# ads.net
KiCad netlist of a schematic drawn in EAGLE
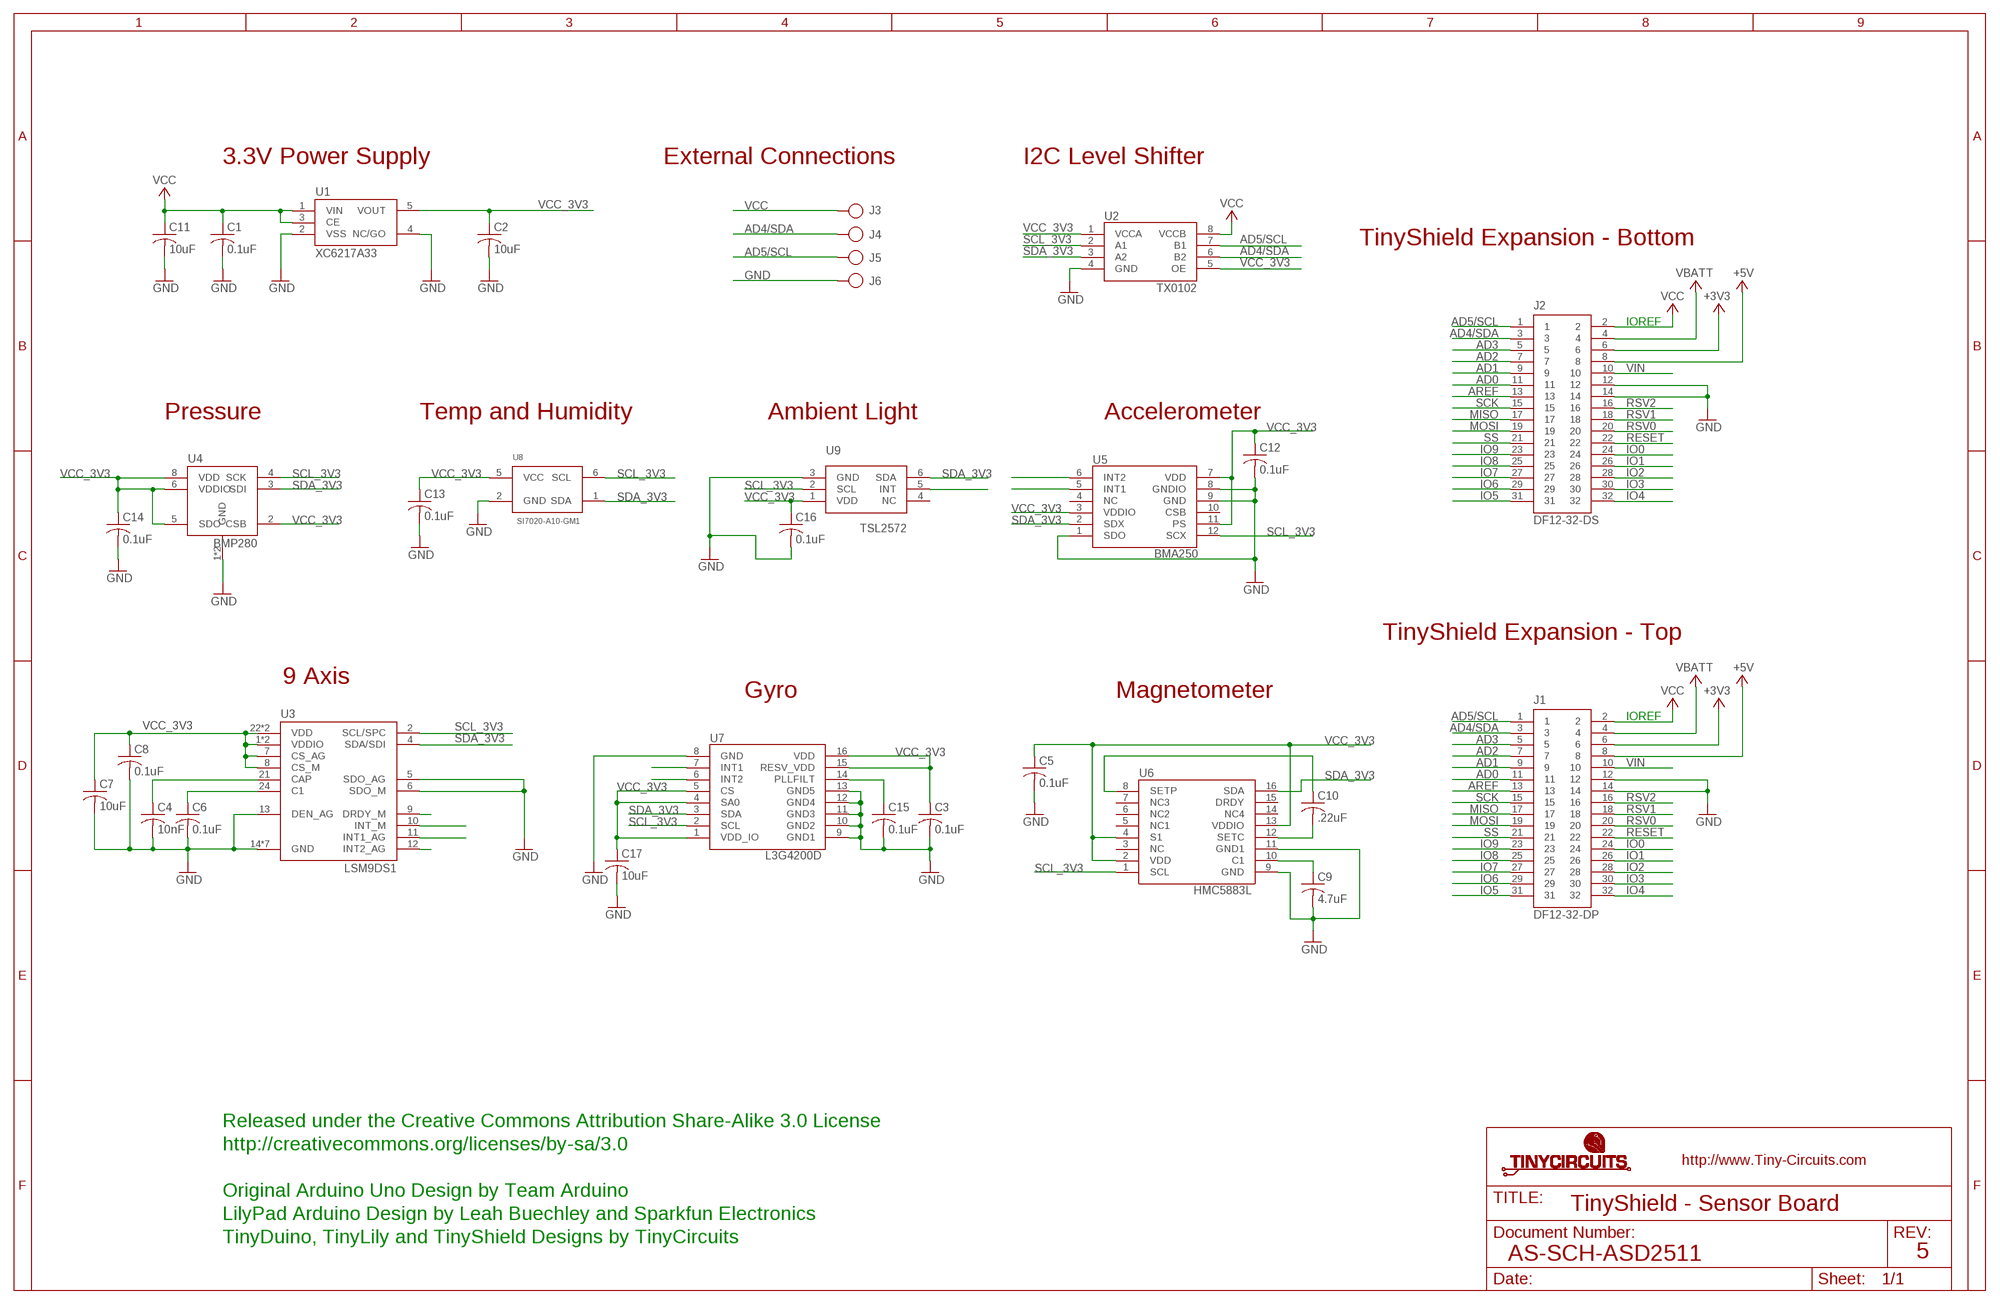
[diagram p0: schematic, sheet 1]

(export (version "E")
  (design (tool "Eeschema 10.0.6"))
  (components
    (comp (ref "C1")
      (value "0.1uF")
      (footprint "eagle-import:C0402")
      (fields (field (name "PARTNO") "AS-ITM-00008") (field (name "PARTNO_1") "AS-ITM-00008"))
      (libsource (lib "eagle-import") (part "AS-ITM-00008"))
    )
    (comp (ref "C2")
      (value "10uF")
      (footprint "eagle-import:C0603")
      (fields (field (name "PARTNO") "AS-ITM-00002") (field (name "PARTNO_1") "AS-ITM-00002"))
      (libsource (lib "eagle-import") (part "AS-ITM-00002"))
    )
    (comp (ref "C3")
      (value "0.1uF")
      (footprint "eagle-import:C0402")
      (fields (field (name "PARTNO") "AS-ITM-00008") (field (name "PARTNO_1") "AS-ITM-00008"))
      (libsource (lib "eagle-import") (part "AS-ITM-00008"))
    )
    (comp (ref "C4")
      (value "10nF")
      (footprint "eagle-import:C0402")
      (fields (field (name "PARTNO") "AS-ITM-00084"))
      (libsource (lib "eagle-import") (part "AS-ITM-00084"))
    )
    (comp (ref "C5")
      (value "0.1uF")
      (footprint "eagle-import:C0402")
      (fields (field (name "PARTNO") "AS-ITM-00008") (field (name "PARTNO_1") "AS-ITM-00008"))
      (libsource (lib "eagle-import") (part "AS-ITM-00008"))
    )
    (comp (ref "C6")
      (value "0.1uF")
      (footprint "eagle-import:C0402")
      (fields (field (name "PARTNO") "AS-ITM-00008"))
      (libsource (lib "eagle-import") (part "AS-ITM-00008"))
    )
    (comp (ref "C7")
      (value "10uF")
      (footprint "eagle-import:C0603")
      (fields (field (name "PARTNO") "AS-ITM-00002") (field (name "PARTNO_1") "AS-ITM-00002"))
      (libsource (lib "eagle-import") (part "AS-ITM-00002"))
    )
    (comp (ref "C8")
      (value "0.1uF")
      (footprint "eagle-import:C0402")
      (fields (field (name "PARTNO") "AS-ITM-00008") (field (name "PARTNO_1") "AS-ITM-00008"))
      (libsource (lib "eagle-import") (part "AS-ITM-00008"))
    )
    (comp (ref "C9")
      (value "4.7uF")
      (footprint "eagle-import:C0402")
      (fields (field (name "PARTNO") "AS-ITM-00242") (field (name "PARTNO_1") "AS-ITM-00242"))
      (libsource (lib "eagle-import") (part "AS-ITM-00242"))
    )
    (comp (ref "C10")
      (value ".22uF")
      (footprint "eagle-import:C0402")
      (fields (field (name "PARTNO") "AS-ITM-00087"))
      (libsource (lib "eagle-import") (part "AS-ITM-00087"))
    )
    (comp (ref "C11")
      (value "10uF")
      (footprint "eagle-import:C0603")
      (fields (field (name "PARTNO") "AS-ITM-00002"))
      (libsource (lib "eagle-import") (part "AS-ITM-00002"))
    )
    (comp (ref "C12")
      (value "0.1uF")
      (footprint "eagle-import:C0402")
      (fields (field (name "PARTNO") "AS-ITM-00008") (field (name "PARTNO_1") "AS-ITM-00008"))
      (libsource (lib "eagle-import") (part "AS-ITM-00008"))
    )
    (comp (ref "C13")
      (value "0.1uF")
      (footprint "eagle-import:C0402")
      (fields (field (name "PARTNO") "AS-ITM-00008") (field (name "PARTNO_1") "AS-ITM-00008"))
      (libsource (lib "eagle-import") (part "AS-ITM-00008"))
    )
    (comp (ref "C14")
      (value "0.1uF")
      (footprint "eagle-import:C0402")
      (fields (field (name "PARTNO") "AS-ITM-00008") (field (name "PARTNO_1") "AS-ITM-00008"))
      (libsource (lib "eagle-import") (part "AS-ITM-00008"))
    )
    (comp (ref "C15")
      (value "0.1uF")
      (footprint "eagle-import:C0402")
      (fields (field (name "PARTNO") "AS-ITM-00008") (field (name "PARTNO_1") "AS-ITM-00008"))
      (libsource (lib "eagle-import") (part "AS-ITM-00008"))
    )
    (comp (ref "C16")
      (value "0.1uF")
      (footprint "eagle-import:C0402")
      (fields (field (name "PARTNO") "AS-ITM-00008") (field (name "PARTNO_1") "AS-ITM-00008"))
      (libsource (lib "eagle-import") (part "AS-ITM-00008"))
    )
    (comp (ref "C17")
      (value "10uF")
      (footprint "eagle-import:C0603")
      (fields (field (name "PARTNO") "AS-ITM-00002"))
      (libsource (lib "eagle-import") (part "AS-ITM-00002"))
    )
    (comp (ref "J1")
      (value "DF12-32-DP")
      (footprint "eagle-import:DF12-32-DP")
      (fields (field (name "PARTNO") "AS-ITM-00015") (field (name "PARTNO_1") "AS-ITM-00015"))
      (libsource (lib "eagle-import") (part "AS-ITM-00015"))
    )
    (comp (ref "J2")
      (value "DF12-32-DS")
      (footprint "eagle-import:DF12-32-DS")
      (fields (field (name "PARTNO") "AS-ITM-00012") (field (name "PARTNO_1") "AS-ITM-00012"))
      (libsource (lib "eagle-import") (part "AS-ITM-00012"))
    )
    (comp (ref "J3")
      (value "PIN_1X.1\"1")
      (footprint "eagle-import:1X.1__2")
      (libsource (lib "eagle-import") (part "PIN_1X.1{dblquote}1"))
    )
    (comp (ref "J4")
      (value "PIN_1X.1\"1")
      (footprint "eagle-import:1X.1__2")
      (libsource (lib "eagle-import") (part "PIN_1X.1{dblquote}1"))
    )
    (comp (ref "J5")
      (value "PIN_1X.1\"1")
      (footprint "eagle-import:1X.1__2")
      (libsource (lib "eagle-import") (part "PIN_1X.1{dblquote}1"))
    )
    (comp (ref "J6")
      (value "PIN_1X.1\"1")
      (footprint "eagle-import:1X.1__2")
      (libsource (lib "eagle-import") (part "PIN_1X.1{dblquote}1"))
    )
    (comp (ref "U1")
      (value "XC6217A33")
      (footprint "eagle-import:SOT-25")
      (fields (field (name "PARTNO") "AS-ITM-00249") (field (name "PARTNO_1") "AS-ITM-00249"))
      (libsource (lib "eagle-import") (part "AS-ITM-00249"))
    )
    (comp (ref "U2")
      (value "TX0102")
      (footprint "eagle-import:DQE(R-PX2SON-N8)")
      (fields (field (name "PARTNO") "AS-ITM-00073"))
      (libsource (lib "eagle-import") (part "AS-ITM-00073"))
    )
    (comp (ref "U3")
      (value "LSM9DS1")
      (footprint "eagle-import:LGA-24")
      (fields (field (name "PARTNO") "AS-ITM-00265"))
      (libsource (lib "eagle-import") (part "AS-ITM-00265"))
    )
    (comp (ref "U4")
      (value "BMP280")
      (footprint "eagle-import:BMP280")
      (fields (field (name "PARTNO") "AS-ITM-00264"))
      (libsource (lib "eagle-import") (part "AS-ITM-00264"))
    )
    (comp (ref "U5")
      (value "BMA250")
      (footprint "eagle-import:3-AXIS_ACCELEROMETER")
      (fields (field (name "PARTNO") "AS-ITM-00070"))
      (libsource (lib "eagle-import") (part "AS-ITM-00070"))
    )
    (comp (ref "U6")
      (value "HMC5883L")
      (footprint "eagle-import:HMC5883L")
      (fields (field (name "PARTNO") "AS-ITM-00086"))
      (libsource (lib "eagle-import") (part "AS-ITM-00086"))
    )
    (comp (ref "U7")
      (value "L3G4200D")
      (footprint "eagle-import:L3G4200D")
      (fields (field (name "PARTNO") "AS-ITM-00089"))
      (libsource (lib "eagle-import") (part "AS-ITM-00089"))
    )
    (comp (ref "U8")
      (value "SI7020-A10-GM1")
      (footprint "eagle-import:DFN6")
      (fields (field (name "PARTNO") "AS-ITM-00218"))
      (libsource (lib "eagle-import") (part "AS-ITM-00218"))
    )
    (comp (ref "U9")
      (value "TSL2572")
      (footprint "eagle-import:TSL2572")
      (fields (field (name "PARTNO") "AS-ITM-00116"))
      (libsource (lib "eagle-import") (part "AS-ITM-00116"))
    )
  )
  (nets
    (net (code "1") (name "+3V3") (class "Default")
      (node (ref "J1") (pin "6") (pinfunction "6_6") (pintype "bidirectional"))
      (node (ref "J2") (pin "6") (pinfunction "6_6") (pintype "bidirectional"))
    )
    (net (code "2") (name "+5V") (class "Default")
      (node (ref "J1") (pin "8") (pinfunction "8_8") (pintype "bidirectional"))
      (node (ref "J2") (pin "8") (pinfunction "8_8") (pintype "bidirectional"))
    )
    (net (code "3") (name "/AD0") (class "Default")
      (node (ref "J1") (pin "11") (pinfunction "11_11") (pintype "bidirectional"))
      (node (ref "J2") (pin "11") (pinfunction "11_11") (pintype "bidirectional"))
    )
    (net (code "4") (name "/AD1") (class "Default")
      (node (ref "J1") (pin "9") (pinfunction "9_9") (pintype "bidirectional"))
      (node (ref "J2") (pin "9") (pinfunction "9_9") (pintype "bidirectional"))
    )
    (net (code "5") (name "/AD2") (class "Default")
      (node (ref "J1") (pin "7") (pinfunction "7_7") (pintype "bidirectional"))
      (node (ref "J2") (pin "7") (pinfunction "7_7") (pintype "bidirectional"))
    )
    (net (code "6") (name "/AD3") (class "Default")
      (node (ref "J1") (pin "5") (pinfunction "5_5") (pintype "bidirectional"))
      (node (ref "J2") (pin "5") (pinfunction "5_5") (pintype "bidirectional"))
    )
    (net (code "7") (name "/AD4{slash}SDA") (class "Default")
      (node (ref "J1") (pin "3") (pinfunction "3_3") (pintype "bidirectional"))
      (node (ref "J2") (pin "3") (pinfunction "3_3") (pintype "bidirectional"))
      (node (ref "J4") (pin "1") (pinfunction "1_1") (pintype "bidirectional"))
      (node (ref "U2") (pin "6") (pinfunction "B2_6") (pintype "bidirectional"))
    )
    (net (code "8") (name "/AD5{slash}SCL") (class "Default")
      (node (ref "J1") (pin "1") (pinfunction "1_1") (pintype "bidirectional"))
      (node (ref "J2") (pin "1") (pinfunction "1_1") (pintype "bidirectional"))
      (node (ref "J5") (pin "1") (pinfunction "1_1") (pintype "bidirectional"))
      (node (ref "U2") (pin "7") (pinfunction "B1_7") (pintype "bidirectional"))
    )
    (net (code "9") (name "/AREF") (class "Default")
      (node (ref "J1") (pin "13") (pinfunction "13_13") (pintype "bidirectional"))
      (node (ref "J2") (pin "13") (pinfunction "13_13") (pintype "bidirectional"))
    )
    (net (code "10") (name "/IO0") (class "Default")
      (node (ref "J1") (pin "24") (pinfunction "24_24") (pintype "bidirectional"))
      (node (ref "J2") (pin "24") (pinfunction "24_24") (pintype "bidirectional"))
    )
    (net (code "11") (name "/IO1") (class "Default")
      (node (ref "J1") (pin "26") (pinfunction "26_26") (pintype "bidirectional"))
      (node (ref "J2") (pin "26") (pinfunction "26_26") (pintype "bidirectional"))
    )
    (net (code "12") (name "/IO2") (class "Default")
      (node (ref "J1") (pin "28") (pinfunction "28_28") (pintype "bidirectional"))
      (node (ref "J2") (pin "28") (pinfunction "28_28") (pintype "bidirectional"))
    )
    (net (code "13") (name "/IO3") (class "Default")
      (node (ref "J1") (pin "30") (pinfunction "30_30") (pintype "bidirectional"))
      (node (ref "J2") (pin "30") (pinfunction "30_30") (pintype "bidirectional"))
    )
    (net (code "14") (name "/IO4") (class "Default")
      (node (ref "J1") (pin "32") (pinfunction "32_32") (pintype "bidirectional"))
      (node (ref "J2") (pin "32") (pinfunction "32_32") (pintype "bidirectional"))
    )
    (net (code "15") (name "/IO5") (class "Default")
      (node (ref "J1") (pin "31") (pinfunction "31_31") (pintype "bidirectional"))
      (node (ref "J2") (pin "31") (pinfunction "31_31") (pintype "bidirectional"))
    )
    (net (code "16") (name "/IO6") (class "Default")
      (node (ref "J1") (pin "29") (pinfunction "29_29") (pintype "bidirectional"))
      (node (ref "J2") (pin "29") (pinfunction "29_29") (pintype "bidirectional"))
    )
    (net (code "17") (name "/IO7") (class "Default")
      (node (ref "J1") (pin "27") (pinfunction "27_27") (pintype "bidirectional"))
      (node (ref "J2") (pin "27") (pinfunction "27_27") (pintype "bidirectional"))
    )
    (net (code "18") (name "/IO8") (class "Default")
      (node (ref "J1") (pin "25") (pinfunction "25_25") (pintype "bidirectional"))
      (node (ref "J2") (pin "25") (pinfunction "25_25") (pintype "bidirectional"))
    )
    (net (code "19") (name "/IO9") (class "Default")
      (node (ref "J1") (pin "23") (pinfunction "23_23") (pintype "bidirectional"))
      (node (ref "J2") (pin "23") (pinfunction "23_23") (pintype "bidirectional"))
    )
    (net (code "20") (name "/MISO") (class "Default")
      (node (ref "J1") (pin "17") (pinfunction "17_17") (pintype "bidirectional"))
      (node (ref "J2") (pin "17") (pinfunction "17_17") (pintype "bidirectional"))
    )
    (net (code "21") (name "/MOSI") (class "Default")
      (node (ref "J1") (pin "19") (pinfunction "19_19") (pintype "bidirectional"))
      (node (ref "J2") (pin "19") (pinfunction "19_19") (pintype "bidirectional"))
    )
    (net (code "22") (name "/RESET") (class "Default")
      (node (ref "J1") (pin "22") (pinfunction "22_22") (pintype "bidirectional"))
      (node (ref "J2") (pin "22") (pinfunction "22_22") (pintype "bidirectional"))
    )
    (net (code "23") (name "/RSV0") (class "Default")
      (node (ref "J1") (pin "20") (pinfunction "20_20") (pintype "bidirectional"))
      (node (ref "J2") (pin "20") (pinfunction "20_20") (pintype "bidirectional"))
    )
    (net (code "24") (name "/RSV1") (class "Default")
      (node (ref "J1") (pin "18") (pinfunction "18_18") (pintype "bidirectional"))
      (node (ref "J2") (pin "18") (pinfunction "18_18") (pintype "bidirectional"))
    )
    (net (code "25") (name "/RSV2") (class "Default")
      (node (ref "J1") (pin "16") (pinfunction "16_16") (pintype "bidirectional"))
      (node (ref "J2") (pin "16") (pinfunction "16_16") (pintype "bidirectional"))
    )
    (net (code "26") (name "/SCK") (class "Default")
      (node (ref "J1") (pin "15") (pinfunction "15_15") (pintype "bidirectional"))
      (node (ref "J2") (pin "15") (pinfunction "15_15") (pintype "bidirectional"))
    )
    (net (code "27") (name "/SCL_3V3") (class "Default")
      (node (ref "U2") (pin "2") (pinfunction "A1_2") (pintype "bidirectional"))
      (node (ref "U3") (pin "2") (pinfunction "SCL/SPC_2") (pintype "bidirectional"))
      (node (ref "U4") (pin "4") (pinfunction "SCK_4") (pintype "bidirectional"))
      (node (ref "U5") (pin "12") (pinfunction "SCX_12") (pintype "bidirectional"))
      (node (ref "U6") (pin "1") (pinfunction "SCL_1") (pintype "bidirectional"))
      (node (ref "U7") (pin "2") (pinfunction "SCL_2") (pintype "bidirectional"))
      (node (ref "U8") (pin "6") (pinfunction "SCL_6") (pintype "bidirectional"))
      (node (ref "U9") (pin "2") (pinfunction "SCL_2") (pintype "bidirectional"))
    )
    (net (code "28") (name "/SDA_3V3") (class "Default")
      (node (ref "U2") (pin "3") (pinfunction "A2_3") (pintype "bidirectional"))
      (node (ref "U3") (pin "4") (pinfunction "SDA/SDI_4") (pintype "bidirectional"))
      (node (ref "U4") (pin "3") (pinfunction "SDI_3") (pintype "bidirectional"))
      (node (ref "U5") (pin "2") (pinfunction "SDX_2") (pintype "bidirectional"))
      (node (ref "U6") (pin "16") (pinfunction "SDA_16") (pintype "bidirectional"))
      (node (ref "U7") (pin "3") (pinfunction "SDA_3") (pintype "bidirectional"))
      (node (ref "U8") (pin "1") (pinfunction "SDA_1") (pintype "bidirectional"))
      (node (ref "U9") (pin "6") (pinfunction "SDA_6") (pintype "bidirectional"))
    )
    (net (code "29") (name "/SS") (class "Default")
      (node (ref "J1") (pin "21") (pinfunction "21_21") (pintype "bidirectional"))
      (node (ref "J2") (pin "21") (pinfunction "21_21") (pintype "bidirectional"))
    )
    (net (code "30") (name "/VCC_3V3") (class "Default")
      (node (ref "C12") (pin "1") (pinfunction "1_1") (pintype "passive"))
      (node (ref "C13") (pin "1") (pinfunction "1_1") (pintype "passive"))
      (node (ref "C14") (pin "1") (pinfunction "1_1") (pintype "passive"))
      (node (ref "C16") (pin "1") (pinfunction "1_1") (pintype "passive"))
      (node (ref "C17") (pin "1") (pinfunction "1_1") (pintype "passive"))
      (node (ref "C2") (pin "1") (pinfunction "1_1") (pintype "passive"))
      (node (ref "C3") (pin "1") (pinfunction "1_1") (pintype "passive"))
      (node (ref "C5") (pin "1") (pinfunction "1_1") (pintype "passive"))
      (node (ref "C7") (pin "1") (pinfunction "1_1") (pintype "passive"))
      (node (ref "C8") (pin "1") (pinfunction "1_1") (pintype "passive"))
      (node (ref "U1") (pin "5") (pinfunction "VOUT_5") (pintype "bidirectional"))
      (node (ref "U2") (pin "1") (pinfunction "VCCA_1") (pintype "bidirectional"))
      (node (ref "U2") (pin "5") (pinfunction "OE_5") (pintype "bidirectional"))
      (node (ref "U3") (pin "1") (pinfunction "VDDIO_1") (pintype "bidirectional"))
      (node (ref "U3") (pin "22") (pinfunction "VDD_22") (pintype "bidirectional"))
      (node (ref "U3") (pin "23") (pinfunction "VDD_23") (pintype "bidirectional"))
      (node (ref "U3") (pin "3") (pinfunction "VDDIO_3") (pintype "bidirectional"))
      (node (ref "U3") (pin "7") (pinfunction "CS_AG_7") (pintype "bidirectional"))
      (node (ref "U3") (pin "8") (pinfunction "CS_M_8") (pintype "bidirectional"))
      (node (ref "U4") (pin "2") (pinfunction "CSB_2") (pintype "bidirectional"))
      (node (ref "U4") (pin "5") (pinfunction "SDO_5") (pintype "bidirectional"))
      (node (ref "U4") (pin "6") (pinfunction "VDDIO_6") (pintype "bidirectional"))
      (node (ref "U4") (pin "8") (pinfunction "VDD_8") (pintype "bidirectional"))
      (node (ref "U5") (pin "11") (pinfunction "PS_11") (pintype "bidirectional"))
      (node (ref "U5") (pin "3") (pinfunction "VDDIO_3") (pintype "bidirectional"))
      (node (ref "U5") (pin "7") (pinfunction "VDD_7") (pintype "bidirectional"))
      (node (ref "U6") (pin "13") (pinfunction "VDDIO_13") (pintype "bidirectional"))
      (node (ref "U6") (pin "2") (pinfunction "VDD_2") (pintype "bidirectional"))
      (node (ref "U6") (pin "4") (pinfunction "S1_4") (pintype "bidirectional"))
      (node (ref "U7") (pin "1") (pinfunction "VDD_IO_1") (pintype "bidirectional"))
      (node (ref "U7") (pin "15") (pinfunction "RESV_VDD_15") (pintype "bidirectional"))
      (node (ref "U7") (pin "16") (pinfunction "VDD_16") (pintype "bidirectional"))
      (node (ref "U7") (pin "4") (pinfunction "SA0_4") (pintype "bidirectional"))
      (node (ref "U7") (pin "5") (pinfunction "CS_5") (pintype "bidirectional"))
      (node (ref "U8") (pin "5") (pinfunction "VCC_5") (pintype "bidirectional"))
      (node (ref "U9") (pin "1") (pinfunction "VDD_1") (pintype "bidirectional"))
    )
    (net (code "31") (name "/VIN") (class "Default")
      (node (ref "J1") (pin "10") (pinfunction "10_10") (pintype "bidirectional"))
      (node (ref "J2") (pin "10") (pinfunction "10_10") (pintype "bidirectional"))
    )
    (net (code "32") (name "GND") (class "Default")
      (node (ref "C1") (pin "2") (pinfunction "2_2") (pintype "passive"))
      (node (ref "C11") (pin "2") (pinfunction "2_2") (pintype "passive"))
      (node (ref "C12") (pin "2") (pinfunction "2_2") (pintype "passive"))
      (node (ref "C13") (pin "2") (pinfunction "2_2") (pintype "passive"))
      (node (ref "C14") (pin "2") (pinfunction "2_2") (pintype "passive"))
      (node (ref "C15") (pin "2") (pinfunction "2_2") (pintype "passive"))
      (node (ref "C16") (pin "2") (pinfunction "2_2") (pintype "passive"))
      (node (ref "C17") (pin "2") (pinfunction "2_2") (pintype "passive"))
      (node (ref "C2") (pin "2") (pinfunction "2_2") (pintype "passive"))
      (node (ref "C3") (pin "2") (pinfunction "2_2") (pintype "passive"))
      (node (ref "C4") (pin "2") (pinfunction "2_2") (pintype "passive"))
      (node (ref "C5") (pin "2") (pinfunction "2_2") (pintype "passive"))
      (node (ref "C6") (pin "2") (pinfunction "2_2") (pintype "passive"))
      (node (ref "C7") (pin "2") (pinfunction "2_2") (pintype "passive"))
      (node (ref "C8") (pin "2") (pinfunction "2_2") (pintype "passive"))
      (node (ref "C9") (pin "2") (pinfunction "2_2") (pintype "passive"))
      (node (ref "J1") (pin "12") (pinfunction "12_12") (pintype "bidirectional"))
      (node (ref "J1") (pin "14") (pinfunction "14_14") (pintype "bidirectional"))
      (node (ref "J2") (pin "12") (pinfunction "12_12") (pintype "bidirectional"))
      (node (ref "J2") (pin "14") (pinfunction "14_14") (pintype "bidirectional"))
      (node (ref "J6") (pin "1") (pinfunction "1_1") (pintype "bidirectional"))
      (node (ref "U1") (pin "2") (pinfunction "VSS_2") (pintype "power_in"))
      (node (ref "U1") (pin "4") (pinfunction "NC/GO_4") (pintype "bidirectional"))
      (node (ref "U2") (pin "4") (pinfunction "GND_4") (pintype "bidirectional"))
      (node (ref "U3") (pin "13") (pinfunction "DEN_AG_13") (pintype "bidirectional"))
      (node (ref "U3") (pin "14") (pinfunction "GND_14") (pintype "bidirectional"))
      (node (ref "U3") (pin "15") (pinfunction "GND_15") (pintype "bidirectional"))
      (node (ref "U3") (pin "16") (pinfunction "GND_16") (pintype "bidirectional"))
      (node (ref "U3") (pin "17") (pinfunction "GND_17") (pintype "bidirectional"))
      (node (ref "U3") (pin "18") (pinfunction "GND_18") (pintype "bidirectional"))
      (node (ref "U3") (pin "19") (pinfunction "GND_19") (pintype "bidirectional"))
      (node (ref "U3") (pin "20") (pinfunction "GND_20") (pintype "bidirectional"))
      (node (ref "U3") (pin "5") (pinfunction "SDO_AG_5") (pintype "bidirectional"))
      (node (ref "U3") (pin "6") (pinfunction "SDO_M_6") (pintype "bidirectional"))
      (node (ref "U4") (pin "1") (pinfunction "GND_1") (pintype "bidirectional"))
      (node (ref "U4") (pin "7") (pinfunction "GND_7") (pintype "bidirectional"))
      (node (ref "U5") (pin "1") (pinfunction "SDO_1") (pintype "bidirectional"))
      (node (ref "U5") (pin "8") (pinfunction "GNDIO_8") (pintype "bidirectional"))
      (node (ref "U5") (pin "9") (pinfunction "GND_9") (pintype "bidirectional"))
      (node (ref "U6") (pin "11") (pinfunction "GND1_11") (pintype "bidirectional"))
      (node (ref "U6") (pin "9") (pinfunction "GND_9") (pintype "bidirectional"))
      (node (ref "U7") (pin "10") (pinfunction "GND2_10") (pintype "bidirectional"))
      (node (ref "U7") (pin "11") (pinfunction "GND3_11") (pintype "bidirectional"))
      (node (ref "U7") (pin "12") (pinfunction "GND4_12") (pintype "bidirectional"))
      (node (ref "U7") (pin "13") (pinfunction "GND5_13") (pintype "bidirectional"))
      (node (ref "U7") (pin "8") (pinfunction "GND_8") (pintype "bidirectional"))
      (node (ref "U7") (pin "9") (pinfunction "GND1_9") (pintype "bidirectional"))
      (node (ref "U8") (pin "2") (pinfunction "GND_2") (pintype "bidirectional"))
      (node (ref "U9") (pin "3") (pinfunction "GND_3") (pintype "bidirectional"))
    )
    (net (code "33") (name "Net-(U3-C1)") (class "Default")
      (node (ref "C6") (pin "1") (pinfunction "1_1") (pintype "passive"))
      (node (ref "U3") (pin "24") (pinfunction "C1_24") (pintype "bidirectional"))
    )
    (net (code "34") (name "Net-(U3-CAP)") (class "Default")
      (node (ref "C4") (pin "1") (pinfunction "1_1") (pintype "passive"))
      (node (ref "U3") (pin "21") (pinfunction "CAP_21") (pintype "bidirectional"))
    )
    (net (code "35") (name "Net-(U6-C1)") (class "Default")
      (node (ref "C9") (pin "1") (pinfunction "1_1") (pintype "passive"))
      (node (ref "U6") (pin "10") (pinfunction "C1_10") (pintype "bidirectional"))
    )
    (net (code "36") (name "Net-(U6-SETC)") (class "Default")
      (node (ref "C10") (pin "2") (pinfunction "2_2") (pintype "passive"))
      (node (ref "U6") (pin "12") (pinfunction "SETC_12") (pintype "bidirectional"))
    )
    (net (code "37") (name "Net-(U6-SETP)") (class "Default")
      (node (ref "C10") (pin "1") (pinfunction "1_1") (pintype "passive"))
      (node (ref "U6") (pin "8") (pinfunction "SETP_8") (pintype "bidirectional"))
    )
    (net (code "38") (name "Net-(U7-PLLFILT)") (class "Default")
      (node (ref "C15") (pin "1") (pinfunction "1_1") (pintype "passive"))
      (node (ref "U7") (pin "14") (pinfunction "PLLFILT_14") (pintype "bidirectional"))
    )
    (net (code "39") (name "VBATT") (class "Default")
      (node (ref "J1") (pin "4") (pinfunction "4_4") (pintype "bidirectional"))
      (node (ref "J2") (pin "4") (pinfunction "4_4") (pintype "bidirectional"))
    )
    (net (code "40") (name "VCC") (class "Default")
      (node (ref "C1") (pin "1") (pinfunction "1_1") (pintype "passive"))
      (node (ref "C11") (pin "1") (pinfunction "1_1") (pintype "passive"))
      (node (ref "J1") (pin "2") (pinfunction "2_2") (pintype "bidirectional"))
      (node (ref "J2") (pin "2") (pinfunction "2_2") (pintype "bidirectional"))
      (node (ref "J3") (pin "1") (pinfunction "1_1") (pintype "bidirectional"))
      (node (ref "U1") (pin "1") (pinfunction "VIN_1") (pintype "bidirectional"))
      (node (ref "U1") (pin "3") (pinfunction "CE_3") (pintype "bidirectional"))
      (node (ref "U2") (pin "8") (pinfunction "VCCB_8") (pintype "bidirectional"))
    )
    (net (code "41") (name "unconnected-(U3-DRDY_M-Pad9)") (class "Default")
      (node (ref "U3") (pin "9") (pinfunction "DRDY_M_9") (pintype "bidirectional"))
    )
    (net (code "42") (name "unconnected-(U3-INT1_AG-Pad11)") (class "Default")
      (node (ref "U3") (pin "11") (pinfunction "INT1_AG_11") (pintype "bidirectional"))
    )
    (net (code "43") (name "unconnected-(U3-INT2_AG-Pad12)") (class "Default")
      (node (ref "U3") (pin "12") (pinfunction "INT2_AG_12") (pintype "bidirectional"))
    )
    (net (code "44") (name "unconnected-(U3-INT_M-Pad10)") (class "Default")
      (node (ref "U3") (pin "10") (pinfunction "INT_M_10") (pintype "bidirectional"))
    )
    (net (code "45") (name "unconnected-(U5-CSB-Pad10)") (class "Default")
      (node (ref "U5") (pin "10") (pinfunction "CSB_10") (pintype "bidirectional"))
    )
    (net (code "46") (name "unconnected-(U5-INT1-Pad5)") (class "Default")
      (node (ref "U5") (pin "5") (pinfunction "INT1_5") (pintype "bidirectional"))
    )
    (net (code "47") (name "unconnected-(U5-INT2-Pad6)") (class "Default")
      (node (ref "U5") (pin "6") (pinfunction "INT2_6") (pintype "bidirectional"))
    )
    (net (code "48") (name "unconnected-(U5-NC-Pad4)") (class "Default")
      (node (ref "U5") (pin "4") (pinfunction "NC_4") (pintype "bidirectional"))
    )
    (net (code "49") (name "unconnected-(U6-DRDY-Pad15)") (class "Default")
      (node (ref "U6") (pin "15") (pinfunction "DRDY_15") (pintype "bidirectional"))
    )
    (net (code "50") (name "unconnected-(U6-NC-Pad3)") (class "Default")
      (node (ref "U6") (pin "3") (pinfunction "NC_3") (pintype "bidirectional"))
    )
    (net (code "51") (name "unconnected-(U6-NC1-Pad5)") (class "Default")
      (node (ref "U6") (pin "5") (pinfunction "NC1_5") (pintype "bidirectional"))
    )
    (net (code "52") (name "unconnected-(U6-NC2-Pad6)") (class "Default")
      (node (ref "U6") (pin "6") (pinfunction "NC2_6") (pintype "bidirectional"))
    )
    (net (code "53") (name "unconnected-(U6-NC3-Pad7)") (class "Default")
      (node (ref "U6") (pin "7") (pinfunction "NC3_7") (pintype "bidirectional"))
    )
    (net (code "54") (name "unconnected-(U6-NC4-Pad14)") (class "Default")
      (node (ref "U6") (pin "14") (pinfunction "NC4_14") (pintype "bidirectional"))
    )
    (net (code "55") (name "unconnected-(U7-INT1-Pad7)") (class "Default")
      (node (ref "U7") (pin "7") (pinfunction "INT1_7") (pintype "bidirectional"))
    )
    (net (code "56") (name "unconnected-(U7-INT2-Pad6)") (class "Default")
      (node (ref "U7") (pin "6") (pinfunction "INT2_6") (pintype "bidirectional"))
    )
    (net (code "57") (name "unconnected-(U9-INT-Pad5)") (class "Default")
      (node (ref "U9") (pin "5") (pinfunction "INT_5") (pintype "bidirectional"))
    )
    (net (code "58") (name "unconnected-(U9-NC-Pad4)") (class "Default")
      (node (ref "U9") (pin "4") (pinfunction "NC_4") (pintype "bidirectional"))
    )
  )
)
